# LSA.net
KiCad netlist of a schematic drawn in EAGLE
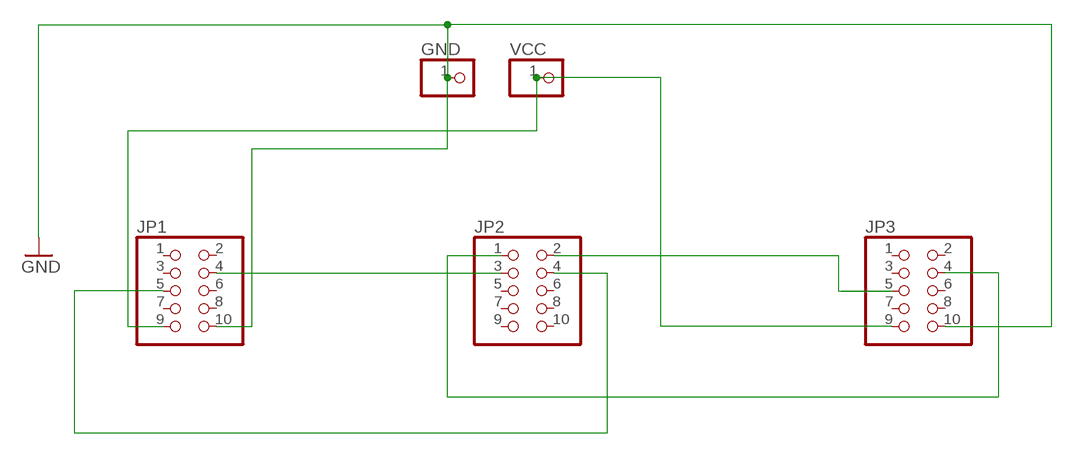
[diagram p0: schematic, sheet 1]

(export (version "E")
  (design (tool "Eeschema 10.0.6"))
  (components
    (comp (ref "GND")
      (value "PINHD-1X1")
      (footprint "eagle-import:1X01")
      (libsource (lib "eagle-import") (part "PINHD-1X1"))
    )
    (comp (ref "JP1")
      (value "PINHD-2X5")
      (footprint "eagle-import:2X05")
      (libsource (lib "eagle-import") (part "PINHD-2X5"))
    )
    (comp (ref "JP2")
      (value "PINHD-2X5")
      (footprint "eagle-import:2X05")
      (libsource (lib "eagle-import") (part "PINHD-2X5"))
    )
    (comp (ref "JP3")
      (value "PINHD-2X5")
      (footprint "eagle-import:2X05")
      (libsource (lib "eagle-import") (part "PINHD-2X5"))
    )
    (comp (ref "VCC")
      (value "PINHD-1X1")
      (footprint "eagle-import:1X01")
      (libsource (lib "eagle-import") (part "PINHD-1X1"))
    )
  )
  (nets
    (net (code "1") (name "GND") (class "Default")
      (node (ref "GND") (pin "1") (pinfunction "1_1") (pintype "passive"))
      (node (ref "JP1") (pin "10") (pinfunction "10_10") (pintype "passive"))
      (node (ref "JP3") (pin "10") (pinfunction "10_10") (pintype "passive"))
    )
    (net (code "2") (name "Net-(JP1-Pad4)") (class "Default")
      (node (ref "JP1") (pin "4") (pinfunction "4_4") (pintype "passive"))
      (node (ref "JP2") (pin "3") (pinfunction "3_3") (pintype "passive"))
    )
    (net (code "3") (name "Net-(JP1-Pad5)") (class "Default")
      (node (ref "JP1") (pin "5") (pinfunction "5_5") (pintype "passive"))
      (node (ref "JP2") (pin "4") (pinfunction "4_4") (pintype "passive"))
    )
    (net (code "4") (name "Net-(JP1-Pad9)") (class "Default")
      (node (ref "JP1") (pin "9") (pinfunction "9_9") (pintype "passive"))
      (node (ref "JP3") (pin "9") (pinfunction "9_9") (pintype "passive"))
      (node (ref "VCC") (pin "1") (pinfunction "1_1") (pintype "passive"))
    )
    (net (code "5") (name "Net-(JP2-Pad1)") (class "Default")
      (node (ref "JP2") (pin "1") (pinfunction "1_1") (pintype "passive"))
      (node (ref "JP3") (pin "4") (pinfunction "4_4") (pintype "passive"))
    )
    (net (code "6") (name "Net-(JP2-Pad2)") (class "Default")
      (node (ref "JP2") (pin "2") (pinfunction "2_2") (pintype "passive"))
      (node (ref "JP3") (pin "5") (pinfunction "5_5") (pintype "passive"))
    )
    (net (code "7") (name "unconnected-(JP1-Pad1)") (class "Default")
      (node (ref "JP1") (pin "1") (pinfunction "1_1") (pintype "passive"))
    )
    (net (code "8") (name "unconnected-(JP1-Pad2)") (class "Default")
      (node (ref "JP1") (pin "2") (pinfunction "2_2") (pintype "passive"))
    )
    (net (code "9") (name "unconnected-(JP1-Pad3)") (class "Default")
      (node (ref "JP1") (pin "3") (pinfunction "3_3") (pintype "passive"))
    )
    (net (code "10") (name "unconnected-(JP1-Pad6)") (class "Default")
      (node (ref "JP1") (pin "6") (pinfunction "6_6") (pintype "passive"))
    )
    (net (code "11") (name "unconnected-(JP1-Pad7)") (class "Default")
      (node (ref "JP1") (pin "7") (pinfunction "7_7") (pintype "passive"))
    )
    (net (code "12") (name "unconnected-(JP1-Pad8)") (class "Default")
      (node (ref "JP1") (pin "8") (pinfunction "8_8") (pintype "passive"))
    )
    (net (code "13") (name "unconnected-(JP2-Pad5)") (class "Default")
      (node (ref "JP2") (pin "5") (pinfunction "5_5") (pintype "passive"))
    )
    (net (code "14") (name "unconnected-(JP2-Pad6)") (class "Default")
      (node (ref "JP2") (pin "6") (pinfunction "6_6") (pintype "passive"))
    )
    (net (code "15") (name "unconnected-(JP2-Pad7)") (class "Default")
      (node (ref "JP2") (pin "7") (pinfunction "7_7") (pintype "passive"))
    )
    (net (code "16") (name "unconnected-(JP2-Pad8)") (class "Default")
      (node (ref "JP2") (pin "8") (pinfunction "8_8") (pintype "passive"))
    )
    (net (code "17") (name "unconnected-(JP2-Pad9)") (class "Default")
      (node (ref "JP2") (pin "9") (pinfunction "9_9") (pintype "passive"))
    )
    (net (code "18") (name "unconnected-(JP2-Pad10)") (class "Default")
      (node (ref "JP2") (pin "10") (pinfunction "10_10") (pintype "passive"))
    )
    (net (code "19") (name "unconnected-(JP3-Pad1)") (class "Default")
      (node (ref "JP3") (pin "1") (pinfunction "1_1") (pintype "passive"))
    )
    (net (code "20") (name "unconnected-(JP3-Pad2)") (class "Default")
      (node (ref "JP3") (pin "2") (pinfunction "2_2") (pintype "passive"))
    )
    (net (code "21") (name "unconnected-(JP3-Pad3)") (class "Default")
      (node (ref "JP3") (pin "3") (pinfunction "3_3") (pintype "passive"))
    )
    (net (code "22") (name "unconnected-(JP3-Pad6)") (class "Default")
      (node (ref "JP3") (pin "6") (pinfunction "6_6") (pintype "passive"))
    )
    (net (code "23") (name "unconnected-(JP3-Pad7)") (class "Default")
      (node (ref "JP3") (pin "7") (pinfunction "7_7") (pintype "passive"))
    )
    (net (code "24") (name "unconnected-(JP3-Pad8)") (class "Default")
      (node (ref "JP3") (pin "8") (pinfunction "8_8") (pintype "passive"))
    )
  )
)
